# BuckBoost5V.net
KiCad netlist of a schematic drawn in Altium Designer
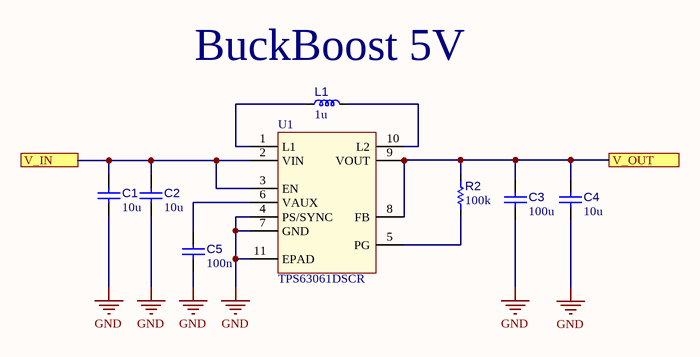
[diagram p0: BuckBoost5V.SchDoc]

(export (version "E")
  (design (tool "Eeschema 10.0.6"))
  (components
    (comp (ref "C1")
      (value "10u")
      (footprint "C_2012[0805]")
      (description "Capacitor type 1")
      (fields (field (name "TOLERANCE") "10%") (field (name "Comment") "CAP CER 10uF 10V X7R 0805"))
      (libsource (lib "TEP-AltiumLib-Passives-RLC") (part "capacitor"))
    )
    (comp (ref "C2")
      (value "10u")
      (footprint "C_2012[0805]")
      (description "Capacitor type 1")
      (fields (field (name "TOLERANCE") "10%") (field (name "Comment") "CAP CER 10uF 10V X7R 0805"))
      (libsource (lib "TEP-AltiumLib-Passives-RLC") (part "capacitor"))
    )
    (comp (ref "C3")
      (value "100u")
      (footprint "C_3216[1206]")
      (description "Capacitor type 1")
      (fields (field (name "TOLERANCE") "20%") (field (name "Comment") "CAP CER 100uF 10V 1206"))
      (libsource (lib "TEP-AltiumLib-Passives-RLC") (part "capacitor"))
    )
    (comp (ref "C4")
      (value "10u")
      (footprint "C_2012[0805]")
      (description "Capacitor type 1")
      (fields (field (name "TOLERANCE") "10%") (field (name "Comment") "CAP CER 10uF 10V X7R 0805"))
      (libsource (lib "TEP-AltiumLib-Passives-RLC") (part "capacitor"))
    )
    (comp (ref "C5")
      (value "100n")
      (footprint "C_1005[0402]")
      (description "Capacitor type 1")
      (fields (field (name "TOLERANCE") "10%") (field (name "Comment") "CAP CER 100nF 50V 0402"))
      (libsource (lib "TEP-AltiumLib-Passives-RLC") (part "capacitor"))
    )
    (comp (ref "L1")
      (value "1u")
      (footprint "L_4040[1515]")
      (description "Inductor type 1")
      (fields (field (name "TOLERANCE") "30%") (field (name "Comment") "Inductor 1UH 3.2A 32mΩ SMD"))
      (libsource (lib "TEP-AltiumLib-Passives-RLC") (part "inductor"))
    )
    (comp (ref "R2")
      (value "100k")
      (footprint "R_1608[0603]")
      (description "Resistor type 1")
      (fields (field (name "TOLERANCE") "1%") (field (name "Comment") "Res 100k 1% 0603"))
      (libsource (lib "TEP-AltiumLib-Passives-RLC") (part "resistor"))
    )
    (comp (ref "U1")
      (value "TPS63061DSCR")
      (footprint "U_WSON50P300X300X80-10N")
      (description "IC REG BUCK BOOST 5V 2A 10WSON")
      (libsource (lib "TEP-AltiumLib-ICs") (part "U_TPS63061DSC"))
    )
  )
  (nets
    (net (code "1") (name "/V_IN") (class "Default")
      (node (ref "C1") (pin "2") (pinfunction "2_2") (pintype "passive"))
      (node (ref "C2") (pin "2") (pinfunction "2_2") (pintype "passive"))
      (node (ref "U1") (pin "2") (pinfunction "VIN_2") (pintype "passive"))
      (node (ref "U1") (pin "3") (pinfunction "EN_3") (pintype "passive"))
    )
    (net (code "2") (name "/V_OUT") (class "Default")
      (node (ref "C3") (pin "2") (pinfunction "2_2") (pintype "passive"))
      (node (ref "C4") (pin "2") (pinfunction "2_2") (pintype "passive"))
      (node (ref "R2") (pin "2") (pinfunction "2_2") (pintype "passive"))
      (node (ref "U1") (pin "8") (pinfunction "FB_8") (pintype "passive"))
      (node (ref "U1") (pin "9") (pinfunction "VOUT_9") (pintype "passive"))
    )
    (net (code "3") (name "GND") (class "Default")
      (node (ref "C1") (pin "1") (pinfunction "1_1") (pintype "passive"))
      (node (ref "C2") (pin "1") (pinfunction "1_1") (pintype "passive"))
      (node (ref "C3") (pin "1") (pinfunction "1_1") (pintype "passive"))
      (node (ref "C4") (pin "1") (pinfunction "1_1") (pintype "passive"))
      (node (ref "C5") (pin "1") (pinfunction "1_1") (pintype "passive"))
      (node (ref "U1") (pin "11") (pinfunction "EPAD_11") (pintype "passive"))
      (node (ref "U1") (pin "4") (pinfunction "PS/SYNC_4") (pintype "passive"))
      (node (ref "U1") (pin "7") (pinfunction "GND_7") (pintype "passive"))
    )
    (net (code "4") (name "Net-(U1-L1)") (class "Default")
      (node (ref "L1") (pin "1") (pinfunction "1_1") (pintype "passive"))
      (node (ref "U1") (pin "1") (pinfunction "L1_1") (pintype "passive"))
    )
    (net (code "5") (name "Net-(U1-L2)") (class "Default")
      (node (ref "L1") (pin "2") (pinfunction "2_2") (pintype "passive"))
      (node (ref "U1") (pin "10") (pinfunction "L2_10") (pintype "passive"))
    )
    (net (code "6") (name "Net-(U1-PG)") (class "Default")
      (node (ref "R2") (pin "1") (pinfunction "1_1") (pintype "passive"))
      (node (ref "U1") (pin "5") (pinfunction "PG_5") (pintype "passive"))
    )
    (net (code "7") (name "Net-(U1-VAUX)") (class "Default")
      (node (ref "C5") (pin "2") (pinfunction "2_2") (pintype "passive"))
      (node (ref "U1") (pin "6") (pinfunction "VAUX_6") (pintype "passive"))
    )
  )
)
